# Rev1.net
KiCad netlist of a schematic drawn in EAGLE
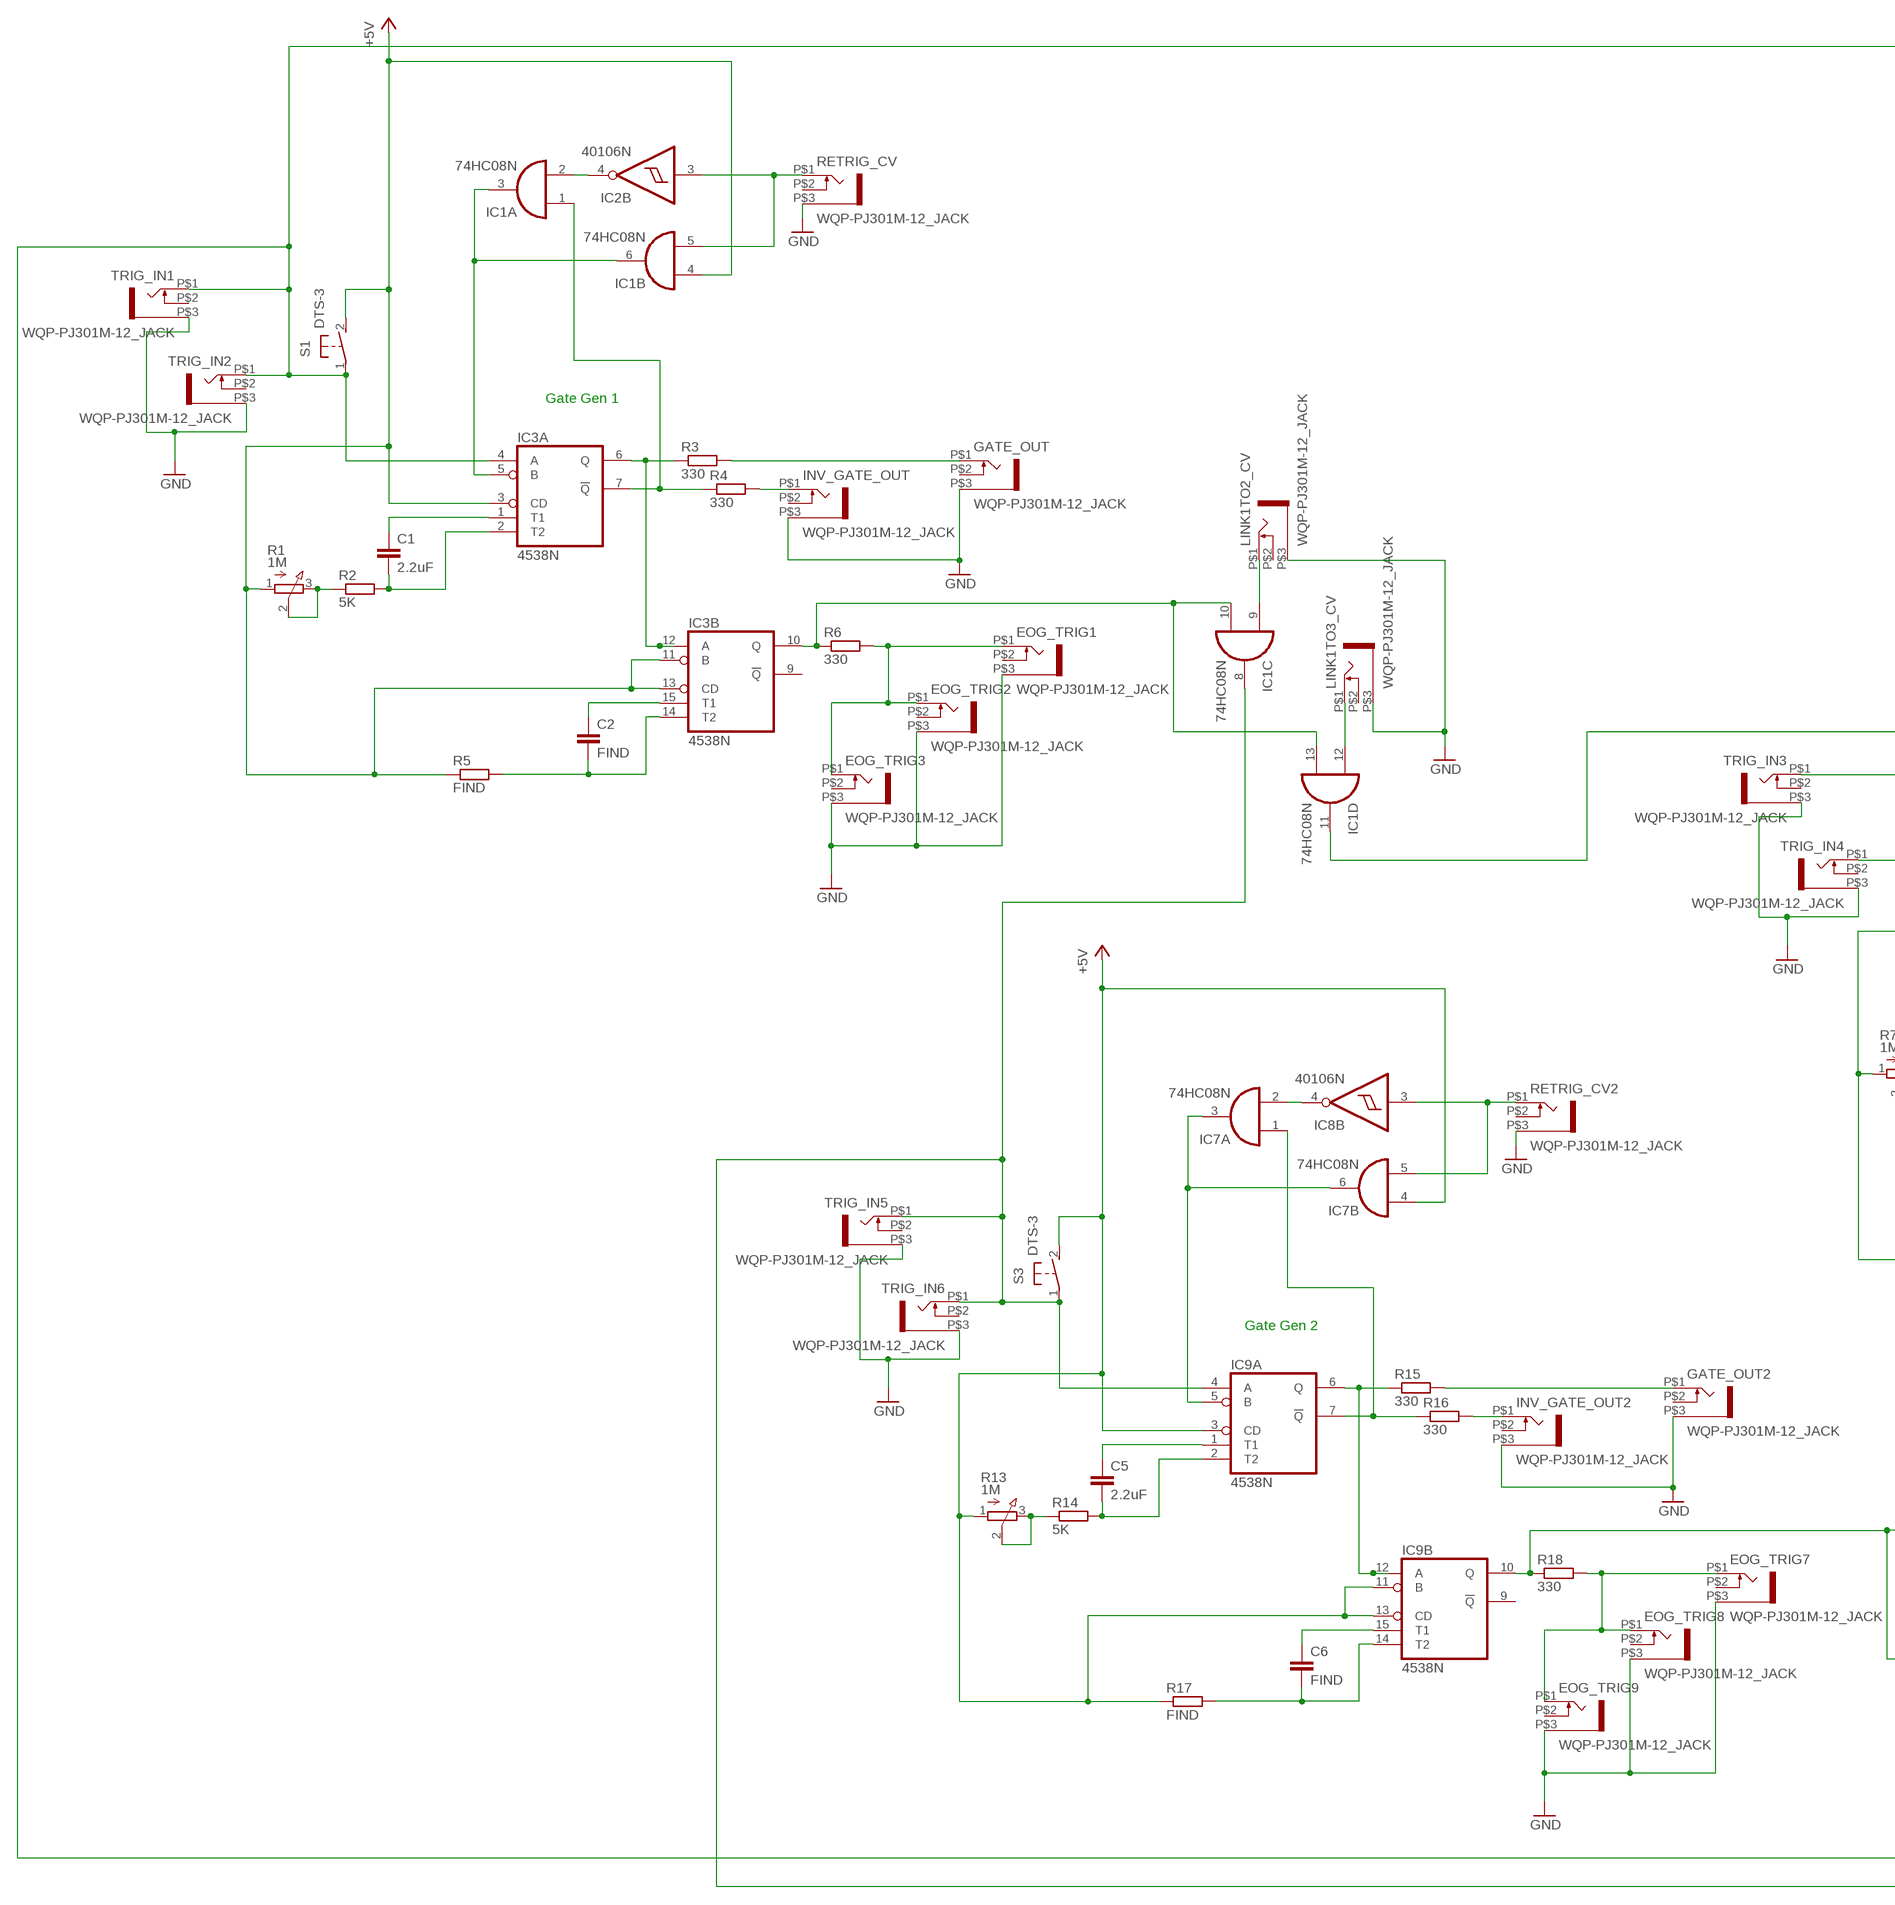
[diagram p0: schematic, sheet 1, part 1 of 2]
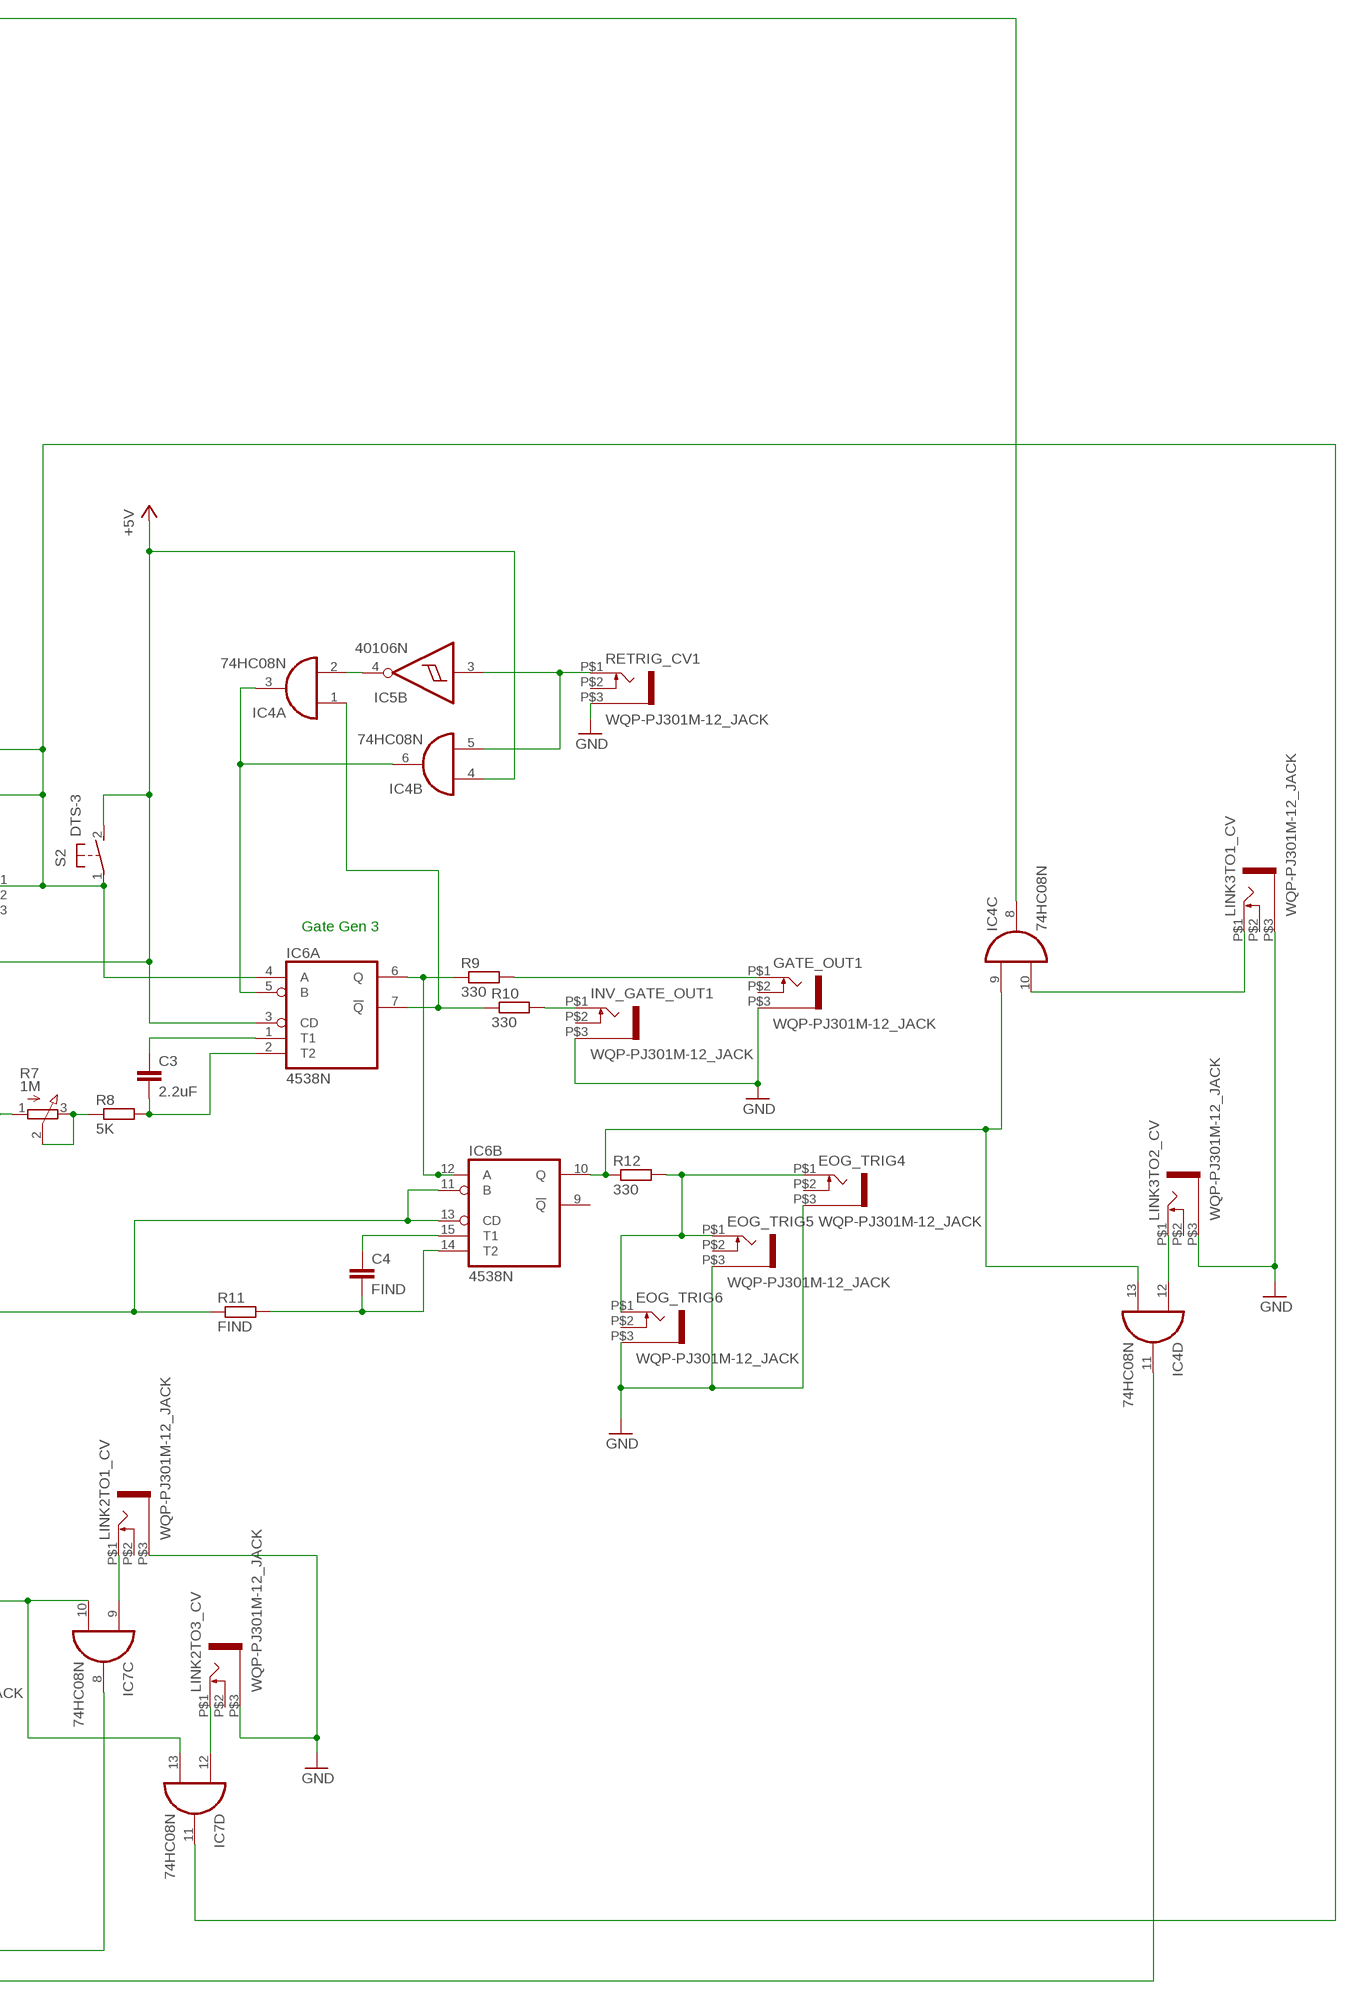
[diagram p1: schematic, sheet 1, part 2 of 2]

(export (version "E")
  (design (tool "Eeschema 10.0.6"))
  (components
    (comp (ref "C1")
      (value "2.2uF")
      (footprint "eagle-import:C2.5-3")
      (libsource (lib "eagle-import") (part "C2,5-3"))
    )
    (comp (ref "C2")
      (value "FIND")
      (footprint "eagle-import:C2.5-3")
      (libsource (lib "eagle-import") (part "C2,5-3"))
    )
    (comp (ref "C3")
      (value "2.2uF")
      (footprint "eagle-import:C2.5-3")
      (libsource (lib "eagle-import") (part "C2,5-3"))
    )
    (comp (ref "C4")
      (value "FIND")
      (footprint "eagle-import:C2.5-3")
      (libsource (lib "eagle-import") (part "C2,5-3"))
    )
    (comp (ref "C5")
      (value "2.2uF")
      (footprint "eagle-import:C2.5-3")
      (libsource (lib "eagle-import") (part "C2,5-3"))
    )
    (comp (ref "C6")
      (value "FIND")
      (footprint "eagle-import:C2.5-3")
      (libsource (lib "eagle-import") (part "C2,5-3"))
    )
    (comp (ref "EOG_TRIG1")
      (value "WQP-PJ301M-12_JACK")
      (footprint "eagle-import:WQP-PJ301M-12_JACK")
      (libsource (lib "eagle-import") (part "WQP-PJ301M-12_JACK"))
    )
    (comp (ref "EOG_TRIG2")
      (value "WQP-PJ301M-12_JACK")
      (footprint "eagle-import:WQP-PJ301M-12_JACK")
      (libsource (lib "eagle-import") (part "WQP-PJ301M-12_JACK"))
    )
    (comp (ref "EOG_TRIG3")
      (value "WQP-PJ301M-12_JACK")
      (footprint "eagle-import:WQP-PJ301M-12_JACK")
      (libsource (lib "eagle-import") (part "WQP-PJ301M-12_JACK"))
    )
    (comp (ref "EOG_TRIG4")
      (value "WQP-PJ301M-12_JACK")
      (footprint "eagle-import:WQP-PJ301M-12_JACK")
      (libsource (lib "eagle-import") (part "WQP-PJ301M-12_JACK"))
    )
    (comp (ref "EOG_TRIG5")
      (value "WQP-PJ301M-12_JACK")
      (footprint "eagle-import:WQP-PJ301M-12_JACK")
      (libsource (lib "eagle-import") (part "WQP-PJ301M-12_JACK"))
    )
    (comp (ref "EOG_TRIG6")
      (value "WQP-PJ301M-12_JACK")
      (footprint "eagle-import:WQP-PJ301M-12_JACK")
      (libsource (lib "eagle-import") (part "WQP-PJ301M-12_JACK"))
    )
    (comp (ref "EOG_TRIG7")
      (value "WQP-PJ301M-12_JACK")
      (footprint "eagle-import:WQP-PJ301M-12_JACK")
      (libsource (lib "eagle-import") (part "WQP-PJ301M-12_JACK"))
    )
    (comp (ref "EOG_TRIG8")
      (value "WQP-PJ301M-12_JACK")
      (footprint "eagle-import:WQP-PJ301M-12_JACK")
      (libsource (lib "eagle-import") (part "WQP-PJ301M-12_JACK"))
    )
    (comp (ref "EOG_TRIG9")
      (value "WQP-PJ301M-12_JACK")
      (footprint "eagle-import:WQP-PJ301M-12_JACK")
      (libsource (lib "eagle-import") (part "WQP-PJ301M-12_JACK"))
    )
    (comp (ref "GATE_OUT")
      (value "WQP-PJ301M-12_JACK")
      (footprint "eagle-import:WQP-PJ301M-12_JACK")
      (libsource (lib "eagle-import") (part "WQP-PJ301M-12_JACK"))
    )
    (comp (ref "GATE_OUT1")
      (value "WQP-PJ301M-12_JACK")
      (footprint "eagle-import:WQP-PJ301M-12_JACK")
      (libsource (lib "eagle-import") (part "WQP-PJ301M-12_JACK"))
    )
    (comp (ref "GATE_OUT2")
      (value "WQP-PJ301M-12_JACK")
      (footprint "eagle-import:WQP-PJ301M-12_JACK")
      (libsource (lib "eagle-import") (part "WQP-PJ301M-12_JACK"))
    )
    (comp (ref "IC1")
      (value "74HC08N")
      (footprint "eagle-import:DIL14")
      (libsource (lib "eagle-import") (part "7408NHC"))
    )
    (comp (ref "IC2")
      (value "40106N")
      (footprint "eagle-import:DIL14")
      (libsource (lib "eagle-import") (part "40106N"))
    )
    (comp (ref "IC3")
      (value "4538N")
      (footprint "eagle-import:DIL16")
      (libsource (lib "eagle-import") (part "4538N"))
    )
    (comp (ref "IC4")
      (value "74HC08N")
      (footprint "eagle-import:DIL14")
      (libsource (lib "eagle-import") (part "7408NHC"))
    )
    (comp (ref "IC5")
      (value "40106N")
      (footprint "eagle-import:DIL14")
      (libsource (lib "eagle-import") (part "40106N"))
    )
    (comp (ref "IC6")
      (value "4538N")
      (footprint "eagle-import:DIL16")
      (libsource (lib "eagle-import") (part "4538N"))
    )
    (comp (ref "IC7")
      (value "74HC08N")
      (footprint "eagle-import:DIL14")
      (libsource (lib "eagle-import") (part "7408NHC"))
    )
    (comp (ref "IC8")
      (value "40106N")
      (footprint "eagle-import:DIL14")
      (libsource (lib "eagle-import") (part "40106N"))
    )
    (comp (ref "IC9")
      (value "4538N")
      (footprint "eagle-import:DIL16")
      (libsource (lib "eagle-import") (part "4538N"))
    )
    (comp (ref "INV_GATE_OUT")
      (value "WQP-PJ301M-12_JACK")
      (footprint "eagle-import:WQP-PJ301M-12_JACK")
      (libsource (lib "eagle-import") (part "WQP-PJ301M-12_JACK"))
    )
    (comp (ref "INV_GATE_OUT1")
      (value "WQP-PJ301M-12_JACK")
      (footprint "eagle-import:WQP-PJ301M-12_JACK")
      (libsource (lib "eagle-import") (part "WQP-PJ301M-12_JACK"))
    )
    (comp (ref "INV_GATE_OUT2")
      (value "WQP-PJ301M-12_JACK")
      (footprint "eagle-import:WQP-PJ301M-12_JACK")
      (libsource (lib "eagle-import") (part "WQP-PJ301M-12_JACK"))
    )
    (comp (ref "LINK1TO2_CV")
      (value "WQP-PJ301M-12_JACK")
      (footprint "eagle-import:WQP-PJ301M-12_JACK")
      (libsource (lib "eagle-import") (part "WQP-PJ301M-12_JACK"))
    )
    (comp (ref "LINK1TO3_CV")
      (value "WQP-PJ301M-12_JACK")
      (footprint "eagle-import:WQP-PJ301M-12_JACK")
      (libsource (lib "eagle-import") (part "WQP-PJ301M-12_JACK"))
    )
    (comp (ref "LINK2TO1_CV")
      (value "WQP-PJ301M-12_JACK")
      (footprint "eagle-import:WQP-PJ301M-12_JACK")
      (libsource (lib "eagle-import") (part "WQP-PJ301M-12_JACK"))
    )
    (comp (ref "LINK2TO3_CV")
      (value "WQP-PJ301M-12_JACK")
      (footprint "eagle-import:WQP-PJ301M-12_JACK")
      (libsource (lib "eagle-import") (part "WQP-PJ301M-12_JACK"))
    )
    (comp (ref "LINK3TO1_CV")
      (value "WQP-PJ301M-12_JACK")
      (footprint "eagle-import:WQP-PJ301M-12_JACK")
      (libsource (lib "eagle-import") (part "WQP-PJ301M-12_JACK"))
    )
    (comp (ref "LINK3TO2_CV")
      (value "WQP-PJ301M-12_JACK")
      (footprint "eagle-import:WQP-PJ301M-12_JACK")
      (libsource (lib "eagle-import") (part "WQP-PJ301M-12_JACK"))
    )
    (comp (ref "R1")
      (value "1M")
      (footprint "eagle-import:3RP_1610N")
      (libsource (lib "eagle-import") (part "3RP/1610N"))
    )
    (comp (ref "R2")
      (value "5K")
      (footprint "eagle-import:0204V")
      (libsource (lib "eagle-import") (part "R-EU_0204/2V"))
    )
    (comp (ref "R3")
      (value "330")
      (footprint "eagle-import:0204V")
      (libsource (lib "eagle-import") (part "R-EU_0204/2V"))
    )
    (comp (ref "R4")
      (value "330")
      (footprint "eagle-import:0204V")
      (libsource (lib "eagle-import") (part "R-EU_0204/2V"))
    )
    (comp (ref "R5")
      (value "FIND")
      (footprint "eagle-import:0204V")
      (libsource (lib "eagle-import") (part "R-EU_0204/2V"))
    )
    (comp (ref "R6")
      (value "330")
      (footprint "eagle-import:0204V")
      (libsource (lib "eagle-import") (part "R-EU_0204/2V"))
    )
    (comp (ref "R7")
      (value "1M")
      (footprint "eagle-import:3RP_1610N")
      (libsource (lib "eagle-import") (part "3RP/1610N"))
    )
    (comp (ref "R8")
      (value "5K")
      (footprint "eagle-import:0204V")
      (libsource (lib "eagle-import") (part "R-EU_0204/2V"))
    )
    (comp (ref "R9")
      (value "330")
      (footprint "eagle-import:0204V")
      (libsource (lib "eagle-import") (part "R-EU_0204/2V"))
    )
    (comp (ref "R10")
      (value "330")
      (footprint "eagle-import:0204V")
      (libsource (lib "eagle-import") (part "R-EU_0204/2V"))
    )
    (comp (ref "R11")
      (value "FIND")
      (footprint "eagle-import:0204V")
      (libsource (lib "eagle-import") (part "R-EU_0204/2V"))
    )
    (comp (ref "R12")
      (value "330")
      (footprint "eagle-import:0204V")
      (libsource (lib "eagle-import") (part "R-EU_0204/2V"))
    )
    (comp (ref "R13")
      (value "1M")
      (footprint "eagle-import:3RP_1610N")
      (libsource (lib "eagle-import") (part "3RP/1610N"))
    )
    (comp (ref "R14")
      (value "5K")
      (footprint "eagle-import:0204V")
      (libsource (lib "eagle-import") (part "R-EU_0204/2V"))
    )
    (comp (ref "R15")
      (value "330")
      (footprint "eagle-import:0204V")
      (libsource (lib "eagle-import") (part "R-EU_0204/2V"))
    )
    (comp (ref "R16")
      (value "330")
      (footprint "eagle-import:0204V")
      (libsource (lib "eagle-import") (part "R-EU_0204/2V"))
    )
    (comp (ref "R17")
      (value "FIND")
      (footprint "eagle-import:0204V")
      (libsource (lib "eagle-import") (part "R-EU_0204/2V"))
    )
    (comp (ref "R18")
      (value "330")
      (footprint "eagle-import:0204V")
      (libsource (lib "eagle-import") (part "R-EU_0204/2V"))
    )
    (comp (ref "RETRIG_CV")
      (value "WQP-PJ301M-12_JACK")
      (footprint "eagle-import:WQP-PJ301M-12_JACK")
      (libsource (lib "eagle-import") (part "WQP-PJ301M-12_JACK"))
    )
    (comp (ref "RETRIG_CV1")
      (value "WQP-PJ301M-12_JACK")
      (footprint "eagle-import:WQP-PJ301M-12_JACK")
      (libsource (lib "eagle-import") (part "WQP-PJ301M-12_JACK"))
    )
    (comp (ref "RETRIG_CV2")
      (value "WQP-PJ301M-12_JACK")
      (footprint "eagle-import:WQP-PJ301M-12_JACK")
      (libsource (lib "eagle-import") (part "WQP-PJ301M-12_JACK"))
    )
    (comp (ref "S1")
      (value "DTS-3")
      (footprint "eagle-import:DTS-3")
      (libsource (lib "eagle-import") (part "DTS-3"))
    )
    (comp (ref "S2")
      (value "DTS-3")
      (footprint "eagle-import:DTS-3")
      (libsource (lib "eagle-import") (part "DTS-3"))
    )
    (comp (ref "S3")
      (value "DTS-3")
      (footprint "eagle-import:DTS-3")
      (libsource (lib "eagle-import") (part "DTS-3"))
    )
    (comp (ref "TRIG_IN1")
      (value "WQP-PJ301M-12_JACK")
      (footprint "eagle-import:WQP-PJ301M-12_JACK")
      (libsource (lib "eagle-import") (part "WQP-PJ301M-12_JACK"))
    )
    (comp (ref "TRIG_IN2")
      (value "WQP-PJ301M-12_JACK")
      (footprint "eagle-import:WQP-PJ301M-12_JACK")
      (libsource (lib "eagle-import") (part "WQP-PJ301M-12_JACK"))
    )
    (comp (ref "TRIG_IN3")
      (value "WQP-PJ301M-12_JACK")
      (footprint "eagle-import:WQP-PJ301M-12_JACK")
      (libsource (lib "eagle-import") (part "WQP-PJ301M-12_JACK"))
    )
    (comp (ref "TRIG_IN4")
      (value "WQP-PJ301M-12_JACK")
      (footprint "eagle-import:WQP-PJ301M-12_JACK")
      (libsource (lib "eagle-import") (part "WQP-PJ301M-12_JACK"))
    )
    (comp (ref "TRIG_IN5")
      (value "WQP-PJ301M-12_JACK")
      (footprint "eagle-import:WQP-PJ301M-12_JACK")
      (libsource (lib "eagle-import") (part "WQP-PJ301M-12_JACK"))
    )
    (comp (ref "TRIG_IN6")
      (value "WQP-PJ301M-12_JACK")
      (footprint "eagle-import:WQP-PJ301M-12_JACK")
      (libsource (lib "eagle-import") (part "WQP-PJ301M-12_JACK"))
    )
  )
  (nets
    (net (code "1") (name "+5V") (class "Default")
      (node (ref "IC1") (pin "4") (pinfunction "I0_4") (pintype "input"))
      (node (ref "IC3") (pin "11") (pinfunction "B_11") (pintype "input"))
      (node (ref "IC3") (pin "13") (pinfunction "CD_13") (pintype "input"))
      (node (ref "IC3") (pin "3") (pinfunction "CD_3") (pintype "input"))
      (node (ref "IC4") (pin "4") (pinfunction "I0_4") (pintype "input"))
      (node (ref "IC6") (pin "11") (pinfunction "B_11") (pintype "input"))
      (node (ref "IC6") (pin "13") (pinfunction "CD_13") (pintype "input"))
      (node (ref "IC6") (pin "3") (pinfunction "CD_3") (pintype "input"))
      (node (ref "IC7") (pin "4") (pinfunction "I0_4") (pintype "input"))
      (node (ref "IC9") (pin "11") (pinfunction "B_11") (pintype "input"))
      (node (ref "IC9") (pin "13") (pinfunction "CD_13") (pintype "input"))
      (node (ref "IC9") (pin "3") (pinfunction "CD_3") (pintype "input"))
      (node (ref "R1") (pin "1") (pinfunction "A_1") (pintype "passive"))
      (node (ref "R11") (pin "1") (pinfunction "1_1") (pintype "passive"))
      (node (ref "R13") (pin "1") (pinfunction "A_1") (pintype "passive"))
      (node (ref "R17") (pin "1") (pinfunction "1_1") (pintype "passive"))
      (node (ref "R5") (pin "1") (pinfunction "1_1") (pintype "passive"))
      (node (ref "R7") (pin "1") (pinfunction "A_1") (pintype "passive"))
      (node (ref "S1") (pin "2") (pinfunction "2_2") (pintype "passive"))
      (node (ref "S2") (pin "2") (pinfunction "2_2") (pintype "passive"))
      (node (ref "S3") (pin "2") (pinfunction "2_2") (pintype "passive"))
    )
    (net (code "2") (name "GND") (class "Default")
      (node (ref "EOG_TRIG1") (pin "P$3") (pinfunction "1_P$3") (pintype "passive"))
      (node (ref "EOG_TRIG2") (pin "P$3") (pinfunction "1_P$3") (pintype "passive"))
      (node (ref "EOG_TRIG3") (pin "P$3") (pinfunction "1_P$3") (pintype "passive"))
      (node (ref "EOG_TRIG4") (pin "P$3") (pinfunction "1_P$3") (pintype "passive"))
      (node (ref "EOG_TRIG5") (pin "P$3") (pinfunction "1_P$3") (pintype "passive"))
      (node (ref "EOG_TRIG6") (pin "P$3") (pinfunction "1_P$3") (pintype "passive"))
      (node (ref "EOG_TRIG7") (pin "P$3") (pinfunction "1_P$3") (pintype "passive"))
      (node (ref "EOG_TRIG8") (pin "P$3") (pinfunction "1_P$3") (pintype "passive"))
      (node (ref "EOG_TRIG9") (pin "P$3") (pinfunction "1_P$3") (pintype "passive"))
      (node (ref "GATE_OUT") (pin "P$3") (pinfunction "1_P$3") (pintype "passive"))
      (node (ref "GATE_OUT1") (pin "P$3") (pinfunction "1_P$3") (pintype "passive"))
      (node (ref "GATE_OUT2") (pin "P$3") (pinfunction "1_P$3") (pintype "passive"))
      (node (ref "INV_GATE_OUT") (pin "P$3") (pinfunction "1_P$3") (pintype "passive"))
      (node (ref "INV_GATE_OUT1") (pin "P$3") (pinfunction "1_P$3") (pintype "passive"))
      (node (ref "INV_GATE_OUT2") (pin "P$3") (pinfunction "1_P$3") (pintype "passive"))
      (node (ref "LINK1TO2_CV") (pin "P$3") (pinfunction "1_P$3") (pintype "passive"))
      (node (ref "LINK1TO3_CV") (pin "P$3") (pinfunction "1_P$3") (pintype "passive"))
      (node (ref "LINK2TO1_CV") (pin "P$3") (pinfunction "1_P$3") (pintype "passive"))
      (node (ref "LINK2TO3_CV") (pin "P$3") (pinfunction "1_P$3") (pintype "passive"))
      (node (ref "LINK3TO1_CV") (pin "P$3") (pinfunction "1_P$3") (pintype "passive"))
      (node (ref "LINK3TO2_CV") (pin "P$3") (pinfunction "1_P$3") (pintype "passive"))
      (node (ref "RETRIG_CV") (pin "P$3") (pinfunction "1_P$3") (pintype "passive"))
      (node (ref "RETRIG_CV1") (pin "P$3") (pinfunction "1_P$3") (pintype "passive"))
      (node (ref "RETRIG_CV2") (pin "P$3") (pinfunction "1_P$3") (pintype "passive"))
      (node (ref "TRIG_IN1") (pin "P$3") (pinfunction "1_P$3") (pintype "passive"))
      (node (ref "TRIG_IN2") (pin "P$3") (pinfunction "1_P$3") (pintype "passive"))
      (node (ref "TRIG_IN3") (pin "P$3") (pinfunction "1_P$3") (pintype "passive"))
      (node (ref "TRIG_IN4") (pin "P$3") (pinfunction "1_P$3") (pintype "passive"))
      (node (ref "TRIG_IN5") (pin "P$3") (pinfunction "1_P$3") (pintype "passive"))
      (node (ref "TRIG_IN6") (pin "P$3") (pinfunction "1_P$3") (pintype "passive"))
    )
    (net (code "3") (name "Net-(EOG_TRIG1-2)") (class "Default")
      (node (ref "EOG_TRIG1") (pin "P$1") (pinfunction "2_P$1") (pintype "passive"))
      (node (ref "EOG_TRIG2") (pin "P$1") (pinfunction "2_P$1") (pintype "passive"))
      (node (ref "EOG_TRIG3") (pin "P$1") (pinfunction "2_P$1") (pintype "passive"))
      (node (ref "R6") (pin "2") (pinfunction "2_2") (pintype "passive"))
    )
    (net (code "4") (name "Net-(EOG_TRIG4-2)") (class "Default")
      (node (ref "EOG_TRIG4") (pin "P$1") (pinfunction "2_P$1") (pintype "passive"))
      (node (ref "EOG_TRIG5") (pin "P$1") (pinfunction "2_P$1") (pintype "passive"))
      (node (ref "EOG_TRIG6") (pin "P$1") (pinfunction "2_P$1") (pintype "passive"))
      (node (ref "R12") (pin "2") (pinfunction "2_2") (pintype "passive"))
    )
    (net (code "5") (name "Net-(EOG_TRIG7-2)") (class "Default")
      (node (ref "EOG_TRIG7") (pin "P$1") (pinfunction "2_P$1") (pintype "passive"))
      (node (ref "EOG_TRIG8") (pin "P$1") (pinfunction "2_P$1") (pintype "passive"))
      (node (ref "EOG_TRIG9") (pin "P$1") (pinfunction "2_P$1") (pintype "passive"))
      (node (ref "R18") (pin "2") (pinfunction "2_2") (pintype "passive"))
    )
    (net (code "6") (name "Net-(GATE_OUT-2)") (class "Default")
      (node (ref "GATE_OUT") (pin "P$1") (pinfunction "2_P$1") (pintype "passive"))
      (node (ref "R3") (pin "2") (pinfunction "2_2") (pintype "passive"))
    )
    (net (code "7") (name "Net-(GATE_OUT1-2)") (class "Default")
      (node (ref "GATE_OUT1") (pin "P$1") (pinfunction "2_P$1") (pintype "passive"))
      (node (ref "R9") (pin "2") (pinfunction "2_2") (pintype "passive"))
    )
    (net (code "8") (name "Net-(GATE_OUT2-2)") (class "Default")
      (node (ref "GATE_OUT2") (pin "P$1") (pinfunction "2_P$1") (pintype "passive"))
      (node (ref "R15") (pin "2") (pinfunction "2_2") (pintype "passive"))
    )
    (net (code "9") (name "Net-(IC1A-I0)") (class "Default")
      (node (ref "IC1") (pin "1") (pinfunction "I0_1") (pintype "input"))
      (node (ref "IC3") (pin "7") (pinfunction "~{Q}_7") (pintype "output"))
      (node (ref "R4") (pin "1") (pinfunction "1_1") (pintype "passive"))
    )
    (net (code "10") (name "Net-(IC1A-I1)") (class "Default")
      (node (ref "IC1") (pin "2") (pinfunction "I1_2") (pintype "input"))
      (node (ref "IC2") (pin "4") (pinfunction "O_4") (pintype "output"))
    )
    (net (code "11") (name "Net-(IC1A-O)") (class "Default")
      (node (ref "IC1") (pin "3") (pinfunction "O_3") (pintype "output"))
      (node (ref "IC1") (pin "6") (pinfunction "O_6") (pintype "output"))
      (node (ref "IC3") (pin "5") (pinfunction "B_5") (pintype "input"))
    )
    (net (code "12") (name "Net-(IC1B-I1)") (class "Default")
      (node (ref "IC1") (pin "5") (pinfunction "I1_5") (pintype "input"))
      (node (ref "IC2") (pin "3") (pinfunction "I_3") (pintype "input"))
      (node (ref "RETRIG_CV") (pin "P$1") (pinfunction "2_P$1") (pintype "passive"))
    )
    (net (code "13") (name "Net-(IC1C-I0)") (class "Default")
      (node (ref "IC1") (pin "9") (pinfunction "I0_9") (pintype "input"))
      (node (ref "LINK1TO2_CV") (pin "P$1") (pinfunction "2_P$1") (pintype "passive"))
    )
    (net (code "14") (name "Net-(IC1C-I1)") (class "Default")
      (node (ref "IC1") (pin "10") (pinfunction "I1_10") (pintype "input"))
      (node (ref "IC1") (pin "13") (pinfunction "I1_13") (pintype "input"))
      (node (ref "IC3") (pin "10") (pinfunction "Q_10") (pintype "output"))
      (node (ref "R6") (pin "1") (pinfunction "1_1") (pintype "passive"))
    )
    (net (code "15") (name "Net-(IC1C-O)") (class "Default")
      (node (ref "IC1") (pin "8") (pinfunction "O_8") (pintype "output"))
      (node (ref "IC4") (pin "11") (pinfunction "O_11") (pintype "output"))
      (node (ref "IC9") (pin "4") (pinfunction "A_4") (pintype "input"))
      (node (ref "S3") (pin "1") (pinfunction "1_1") (pintype "passive"))
      (node (ref "TRIG_IN5") (pin "P$1") (pinfunction "2_P$1") (pintype "passive"))
      (node (ref "TRIG_IN6") (pin "P$1") (pinfunction "2_P$1") (pintype "passive"))
    )
    (net (code "16") (name "Net-(IC1D-I0)") (class "Default")
      (node (ref "IC1") (pin "12") (pinfunction "I0_12") (pintype "input"))
      (node (ref "LINK1TO3_CV") (pin "P$1") (pinfunction "2_P$1") (pintype "passive"))
    )
    (net (code "17") (name "Net-(IC1D-O)") (class "Default")
      (node (ref "IC1") (pin "11") (pinfunction "O_11") (pintype "output"))
      (node (ref "IC6") (pin "4") (pinfunction "A_4") (pintype "input"))
      (node (ref "IC7") (pin "11") (pinfunction "O_11") (pintype "output"))
      (node (ref "S2") (pin "1") (pinfunction "1_1") (pintype "passive"))
      (node (ref "TRIG_IN3") (pin "P$1") (pinfunction "2_P$1") (pintype "passive"))
      (node (ref "TRIG_IN4") (pin "P$1") (pinfunction "2_P$1") (pintype "passive"))
    )
    (net (code "18") (name "Net-(IC3A-A)") (class "Default")
      (node (ref "IC3") (pin "4") (pinfunction "A_4") (pintype "input"))
      (node (ref "IC4") (pin "8") (pinfunction "O_8") (pintype "output"))
      (node (ref "IC7") (pin "8") (pinfunction "O_8") (pintype "output"))
      (node (ref "S1") (pin "1") (pinfunction "1_1") (pintype "passive"))
      (node (ref "TRIG_IN1") (pin "P$1") (pinfunction "2_P$1") (pintype "passive"))
      (node (ref "TRIG_IN2") (pin "P$1") (pinfunction "2_P$1") (pintype "passive"))
    )
    (net (code "19") (name "Net-(IC3A-Q)") (class "Default")
      (node (ref "IC3") (pin "12") (pinfunction "A_12") (pintype "input"))
      (node (ref "IC3") (pin "6") (pinfunction "Q_6") (pintype "output"))
      (node (ref "R3") (pin "1") (pinfunction "1_1") (pintype "passive"))
    )
    (net (code "20") (name "Net-(IC3A-T1)") (class "Default")
      (node (ref "C1") (pin "1") (pinfunction "1_1") (pintype "passive"))
      (node (ref "IC3") (pin "1") (pinfunction "T1_1") (pintype "input"))
    )
    (net (code "21") (name "Net-(IC3A-T2)") (class "Default")
      (node (ref "C1") (pin "2") (pinfunction "2_2") (pintype "passive"))
      (node (ref "IC3") (pin "2") (pinfunction "T2_2") (pintype "input"))
      (node (ref "R2") (pin "2") (pinfunction "2_2") (pintype "passive"))
    )
    (net (code "22") (name "Net-(IC3B-T1)") (class "Default")
      (node (ref "C2") (pin "1") (pinfunction "1_1") (pintype "passive"))
      (node (ref "IC3") (pin "15") (pinfunction "T1_15") (pintype "input"))
    )
    (net (code "23") (name "Net-(IC3B-T2)") (class "Default")
      (node (ref "C2") (pin "2") (pinfunction "2_2") (pintype "passive"))
      (node (ref "IC3") (pin "14") (pinfunction "T2_14") (pintype "input"))
      (node (ref "R5") (pin "2") (pinfunction "2_2") (pintype "passive"))
    )
    (net (code "24") (name "Net-(IC4A-I0)") (class "Default")
      (node (ref "IC4") (pin "1") (pinfunction "I0_1") (pintype "input"))
      (node (ref "IC6") (pin "7") (pinfunction "~{Q}_7") (pintype "output"))
      (node (ref "R10") (pin "1") (pinfunction "1_1") (pintype "passive"))
    )
    (net (code "25") (name "Net-(IC4A-I1)") (class "Default")
      (node (ref "IC4") (pin "2") (pinfunction "I1_2") (pintype "input"))
      (node (ref "IC5") (pin "4") (pinfunction "O_4") (pintype "output"))
    )
    (net (code "26") (name "Net-(IC4A-O)") (class "Default")
      (node (ref "IC4") (pin "3") (pinfunction "O_3") (pintype "output"))
      (node (ref "IC4") (pin "6") (pinfunction "O_6") (pintype "output"))
      (node (ref "IC6") (pin "5") (pinfunction "B_5") (pintype "input"))
    )
    (net (code "27") (name "Net-(IC4B-I1)") (class "Default")
      (node (ref "IC4") (pin "5") (pinfunction "I1_5") (pintype "input"))
      (node (ref "IC5") (pin "3") (pinfunction "I_3") (pintype "input"))
      (node (ref "RETRIG_CV1") (pin "P$1") (pinfunction "2_P$1") (pintype "passive"))
    )
    (net (code "28") (name "Net-(IC4C-I0)") (class "Default")
      (node (ref "IC4") (pin "13") (pinfunction "I1_13") (pintype "input"))
      (node (ref "IC4") (pin "9") (pinfunction "I0_9") (pintype "input"))
      (node (ref "IC6") (pin "10") (pinfunction "Q_10") (pintype "output"))
      (node (ref "R12") (pin "1") (pinfunction "1_1") (pintype "passive"))
    )
    (net (code "29") (name "Net-(IC4C-I1)") (class "Default")
      (node (ref "IC4") (pin "10") (pinfunction "I1_10") (pintype "input"))
      (node (ref "LINK3TO1_CV") (pin "P$1") (pinfunction "2_P$1") (pintype "passive"))
    )
    (net (code "30") (name "Net-(IC4D-I0)") (class "Default")
      (node (ref "IC4") (pin "12") (pinfunction "I0_12") (pintype "input"))
      (node (ref "LINK3TO2_CV") (pin "P$1") (pinfunction "2_P$1") (pintype "passive"))
    )
    (net (code "31") (name "Net-(IC6A-Q)") (class "Default")
      (node (ref "IC6") (pin "12") (pinfunction "A_12") (pintype "input"))
      (node (ref "IC6") (pin "6") (pinfunction "Q_6") (pintype "output"))
      (node (ref "R9") (pin "1") (pinfunction "1_1") (pintype "passive"))
    )
    (net (code "32") (name "Net-(IC6A-T1)") (class "Default")
      (node (ref "C3") (pin "1") (pinfunction "1_1") (pintype "passive"))
      (node (ref "IC6") (pin "1") (pinfunction "T1_1") (pintype "input"))
    )
    (net (code "33") (name "Net-(IC6A-T2)") (class "Default")
      (node (ref "C3") (pin "2") (pinfunction "2_2") (pintype "passive"))
      (node (ref "IC6") (pin "2") (pinfunction "T2_2") (pintype "input"))
      (node (ref "R8") (pin "2") (pinfunction "2_2") (pintype "passive"))
    )
    (net (code "34") (name "Net-(IC6B-T1)") (class "Default")
      (node (ref "C4") (pin "1") (pinfunction "1_1") (pintype "passive"))
      (node (ref "IC6") (pin "15") (pinfunction "T1_15") (pintype "input"))
    )
    (net (code "35") (name "Net-(IC6B-T2)") (class "Default")
      (node (ref "C4") (pin "2") (pinfunction "2_2") (pintype "passive"))
      (node (ref "IC6") (pin "14") (pinfunction "T2_14") (pintype "input"))
      (node (ref "R11") (pin "2") (pinfunction "2_2") (pintype "passive"))
    )
    (net (code "36") (name "Net-(IC7A-I0)") (class "Default")
      (node (ref "IC7") (pin "1") (pinfunction "I0_1") (pintype "input"))
      (node (ref "IC9") (pin "7") (pinfunction "~{Q}_7") (pintype "output"))
      (node (ref "R16") (pin "1") (pinfunction "1_1") (pintype "passive"))
    )
    (net (code "37") (name "Net-(IC7A-I1)") (class "Default")
      (node (ref "IC7") (pin "2") (pinfunction "I1_2") (pintype "input"))
      (node (ref "IC8") (pin "4") (pinfunction "O_4") (pintype "output"))
    )
    (net (code "38") (name "Net-(IC7A-O)") (class "Default")
      (node (ref "IC7") (pin "3") (pinfunction "O_3") (pintype "output"))
      (node (ref "IC7") (pin "6") (pinfunction "O_6") (pintype "output"))
      (node (ref "IC9") (pin "5") (pinfunction "B_5") (pintype "input"))
    )
    (net (code "39") (name "Net-(IC7B-I1)") (class "Default")
      (node (ref "IC7") (pin "5") (pinfunction "I1_5") (pintype "input"))
      (node (ref "IC8") (pin "3") (pinfunction "I_3") (pintype "input"))
      (node (ref "RETRIG_CV2") (pin "P$1") (pinfunction "2_P$1") (pintype "passive"))
    )
    (net (code "40") (name "Net-(IC7C-I0)") (class "Default")
      (node (ref "IC7") (pin "9") (pinfunction "I0_9") (pintype "input"))
      (node (ref "LINK2TO1_CV") (pin "P$1") (pinfunction "2_P$1") (pintype "passive"))
    )
    (net (code "41") (name "Net-(IC7C-I1)") (class "Default")
      (node (ref "IC7") (pin "10") (pinfunction "I1_10") (pintype "input"))
      (node (ref "IC7") (pin "13") (pinfunction "I1_13") (pintype "input"))
      (node (ref "IC9") (pin "10") (pinfunction "Q_10") (pintype "output"))
      (node (ref "R18") (pin "1") (pinfunction "1_1") (pintype "passive"))
    )
    (net (code "42") (name "Net-(IC7D-I0)") (class "Default")
      (node (ref "IC7") (pin "12") (pinfunction "I0_12") (pintype "input"))
      (node (ref "LINK2TO3_CV") (pin "P$1") (pinfunction "2_P$1") (pintype "passive"))
    )
    (net (code "43") (name "Net-(IC9A-Q)") (class "Default")
      (node (ref "IC9") (pin "12") (pinfunction "A_12") (pintype "input"))
      (node (ref "IC9") (pin "6") (pinfunction "Q_6") (pintype "output"))
      (node (ref "R15") (pin "1") (pinfunction "1_1") (pintype "passive"))
    )
    (net (code "44") (name "Net-(IC9A-T1)") (class "Default")
      (node (ref "C5") (pin "1") (pinfunction "1_1") (pintype "passive"))
      (node (ref "IC9") (pin "1") (pinfunction "T1_1") (pintype "input"))
    )
    (net (code "45") (name "Net-(IC9A-T2)") (class "Default")
      (node (ref "C5") (pin "2") (pinfunction "2_2") (pintype "passive"))
      (node (ref "IC9") (pin "2") (pinfunction "T2_2") (pintype "input"))
      (node (ref "R14") (pin "2") (pinfunction "2_2") (pintype "passive"))
    )
    (net (code "46") (name "Net-(IC9B-T1)") (class "Default")
      (node (ref "C6") (pin "1") (pinfunction "1_1") (pintype "passive"))
      (node (ref "IC9") (pin "15") (pinfunction "T1_15") (pintype "input"))
    )
    (net (code "47") (name "Net-(IC9B-T2)") (class "Default")
      (node (ref "C6") (pin "2") (pinfunction "2_2") (pintype "passive"))
      (node (ref "IC9") (pin "14") (pinfunction "T2_14") (pintype "input"))
      (node (ref "R17") (pin "2") (pinfunction "2_2") (pintype "passive"))
    )
    (net (code "48") (name "Net-(INV_GATE_OUT-2)") (class "Default")
      (node (ref "INV_GATE_OUT") (pin "P$1") (pinfunction "2_P$1") (pintype "passive"))
      (node (ref "R4") (pin "2") (pinfunction "2_2") (pintype "passive"))
    )
    (net (code "49") (name "Net-(INV_GATE_OUT1-2)") (class "Default")
      (node (ref "INV_GATE_OUT1") (pin "P$1") (pinfunction "2_P$1") (pintype "passive"))
      (node (ref "R10") (pin "2") (pinfunction "2_2") (pintype "passive"))
    )
    (net (code "50") (name "Net-(INV_GATE_OUT2-2)") (class "Default")
      (node (ref "INV_GATE_OUT2") (pin "P$1") (pinfunction "2_P$1") (pintype "passive"))
      (node (ref "R16") (pin "2") (pinfunction "2_2") (pintype "passive"))
    )
    (net (code "51") (name "Net-(R1-E)") (class "Default")
      (node (ref "R1") (pin "2") (pinfunction "S_2") (pintype "passive"))
      (node (ref "R1") (pin "3") (pinfunction "E_3") (pintype "passive"))
      (node (ref "R2") (pin "1") (pinfunction "1_1") (pintype "passive"))
    )
    (net (code "52") (name "Net-(R7-E)") (class "Default")
      (node (ref "R7") (pin "2") (pinfunction "S_2") (pintype "passive"))
      (node (ref "R7") (pin "3") (pinfunction "E_3") (pintype "passive"))
      (node (ref "R8") (pin "1") (pinfunction "1_1") (pintype "passive"))
    )
    (net (code "53") (name "Net-(R13-E)") (class "Default")
      (node (ref "R13") (pin "2") (pinfunction "S_2") (pintype "passive"))
      (node (ref "R13") (pin "3") (pinfunction "E_3") (pintype "passive"))
      (node (ref "R14") (pin "1") (pinfunction "1_1") (pintype "passive"))
    )
    (net (code "54") (name "unconnected-(EOG_TRIG1-3-PadP$2)") (class "Default")
      (node (ref "EOG_TRIG1") (pin "P$2") (pinfunction "3_P$2") (pintype "passive"))
    )
    (net (code "55") (name "unconnected-(EOG_TRIG2-3-PadP$2)") (class "Default")
      (node (ref "EOG_TRIG2") (pin "P$2") (pinfunction "3_P$2") (pintype "passive"))
    )
    (net (code "56") (name "unconnected-(EOG_TRIG3-3-PadP$2)") (class "Default")
      (node (ref "EOG_TRIG3") (pin "P$2") (pinfunction "3_P$2") (pintype "passive"))
    )
    (net (code "57") (name "unconnected-(EOG_TRIG4-3-PadP$2)") (class "Default")
      (node (ref "EOG_TRIG4") (pin "P$2") (pinfunction "3_P$2") (pintype "passive"))
    )
    (net (code "58") (name "unconnected-(EOG_TRIG5-3-PadP$2)") (class "Default")
      (node (ref "EOG_TRIG5") (pin "P$2") (pinfunction "3_P$2") (pintype "passive"))
    )
    (net (code "59") (name "unconnected-(EOG_TRIG6-3-PadP$2)") (class "Default")
      (node (ref "EOG_TRIG6") (pin "P$2") (pinfunction "3_P$2") (pintype "passive"))
    )
    (net (code "60") (name "unconnected-(EOG_TRIG7-3-PadP$2)") (class "Default")
      (node (ref "EOG_TRIG7") (pin "P$2") (pinfunction "3_P$2") (pintype "passive"))
    )
    (net (code "61") (name "unconnected-(EOG_TRIG8-3-PadP$2)") (class "Default")
      (node (ref "EOG_TRIG8") (pin "P$2") (pinfunction "3_P$2") (pintype "passive"))
    )
    (net (code "62") (name "unconnected-(EOG_TRIG9-3-PadP$2)") (class "Default")
      (node (ref "EOG_TRIG9") (pin "P$2") (pinfunction "3_P$2") (pintype "passive"))
    )
    (net (code "63") (name "unconnected-(GATE_OUT-3-PadP$2)") (class "Default")
      (node (ref "GATE_OUT") (pin "P$2") (pinfunction "3_P$2") (pintype "passive"))
    )
    (net (code "64") (name "unconnected-(GATE_OUT1-3-PadP$2)") (class "Default")
      (node (ref "GATE_OUT1") (pin "P$2") (pinfunction "3_P$2") (pintype "passive"))
    )
    (net (code "65") (name "unconnected-(GATE_OUT2-3-PadP$2)") (class "Default")
      (node (ref "GATE_OUT2") (pin "P$2") (pinfunction "3_P$2") (pintype "passive"))
    )
    (net (code "66") (name "unconnected-(IC3B-~{Q}-Pad9)") (class "Default")
      (node (ref "IC3") (pin "9") (pinfunction "~{Q}_9") (pintype "output"))
    )
    (net (code "67") (name "unconnected-(IC6B-~{Q}-Pad9)") (class "Default")
      (node (ref "IC6") (pin "9") (pinfunction "~{Q}_9") (pintype "output"))
    )
    (net (code "68") (name "unconnected-(IC9B-~{Q}-Pad9)") (class "Default")
      (node (ref "IC9") (pin "9") (pinfunction "~{Q}_9") (pintype "output"))
    )
    (net (code "69") (name "unconnected-(INV_GATE_OUT-3-PadP$2)") (class "Default")
      (node (ref "INV_GATE_OUT") (pin "P$2") (pinfunction "3_P$2") (pintype "passive"))
    )
    (net (code "70") (name "unconnected-(INV_GATE_OUT1-3-PadP$2)") (class "Default")
      (node (ref "INV_GATE_OUT1") (pin "P$2") (pinfunction "3_P$2") (pintype "passive"))
    )
    (net (code "71") (name "unconnected-(INV_GATE_OUT2-3-PadP$2)") (class "Default")
      (node (ref "INV_GATE_OUT2") (pin "P$2") (pinfunction "3_P$2") (pintype "passive"))
    )
    (net (code "72") (name "unconnected-(LINK1TO2_CV-3-PadP$2)") (class "Default")
      (node (ref "LINK1TO2_CV") (pin "P$2") (pinfunction "3_P$2") (pintype "passive"))
    )
    (net (code "73") (name "unconnected-(LINK1TO3_CV-3-PadP$2)") (class "Default")
      (node (ref "LINK1TO3_CV") (pin "P$2") (pinfunction "3_P$2") (pintype "passive"))
    )
    (net (code "74") (name "unconnected-(LINK2TO1_CV-3-PadP$2)") (class "Default")
      (node (ref "LINK2TO1_CV") (pin "P$2") (pinfunction "3_P$2") (pintype "passive"))
    )
    (net (code "75") (name "unconnected-(LINK2TO3_CV-3-PadP$2)") (class "Default")
      (node (ref "LINK2TO3_CV") (pin "P$2") (pinfunction "3_P$2") (pintype "passive"))
    )
    (net (code "76") (name "unconnected-(LINK3TO1_CV-3-PadP$2)") (class "Default")
      (node (ref "LINK3TO1_CV") (pin "P$2") (pinfunction "3_P$2") (pintype "passive"))
    )
    (net (code "77") (name "unconnected-(LINK3TO2_CV-3-PadP$2)") (class "Default")
      (node (ref "LINK3TO2_CV") (pin "P$2") (pinfunction "3_P$2") (pintype "passive"))
    )
    (net (code "78") (name "unconnected-(RETRIG_CV-3-PadP$2)") (class "Default")
      (node (ref "RETRIG_CV") (pin "P$2") (pinfunction "3_P$2") (pintype "passive"))
    )
    (net (code "79") (name "unconnected-(RETRIG_CV1-3-PadP$2)") (class "Default")
      (node (ref "RETRIG_CV1") (pin "P$2") (pinfunction "3_P$2") (pintype "passive"))
    )
    (net (code "80") (name "unconnected-(RETRIG_CV2-3-PadP$2)") (class "Default")
      (node (ref "RETRIG_CV2") (pin "P$2") (pinfunction "3_P$2") (pintype "passive"))
    )
    (net (code "81") (name "unconnected-(TRIG_IN1-3-PadP$2)") (class "Default")
      (node (ref "TRIG_IN1") (pin "P$2") (pinfunction "3_P$2") (pintype "passive"))
    )
    (net (code "82") (name "unconnected-(TRIG_IN2-3-PadP$2)") (class "Default")
      (node (ref "TRIG_IN2") (pin "P$2") (pinfunction "3_P$2") (pintype "passive"))
    )
    (net (code "83") (name "unconnected-(TRIG_IN3-3-PadP$2)") (class "Default")
      (node (ref "TRIG_IN3") (pin "P$2") (pinfunction "3_P$2") (pintype "passive"))
    )
    (net (code "84") (name "unconnected-(TRIG_IN4-3-PadP$2)") (class "Default")
      (node (ref "TRIG_IN4") (pin "P$2") (pinfunction "3_P$2") (pintype "passive"))
    )
    (net (code "85") (name "unconnected-(TRIG_IN5-3-PadP$2)") (class "Default")
      (node (ref "TRIG_IN5") (pin "P$2") (pinfunction "3_P$2") (pintype "passive"))
    )
    (net (code "86") (name "unconnected-(TRIG_IN6-3-PadP$2)") (class "Default")
      (node (ref "TRIG_IN6") (pin "P$2") (pinfunction "3_P$2") (pintype "passive"))
    )
  )
)
